# Main_3.net
KiCad netlist of a schematic drawn in Altium Designer
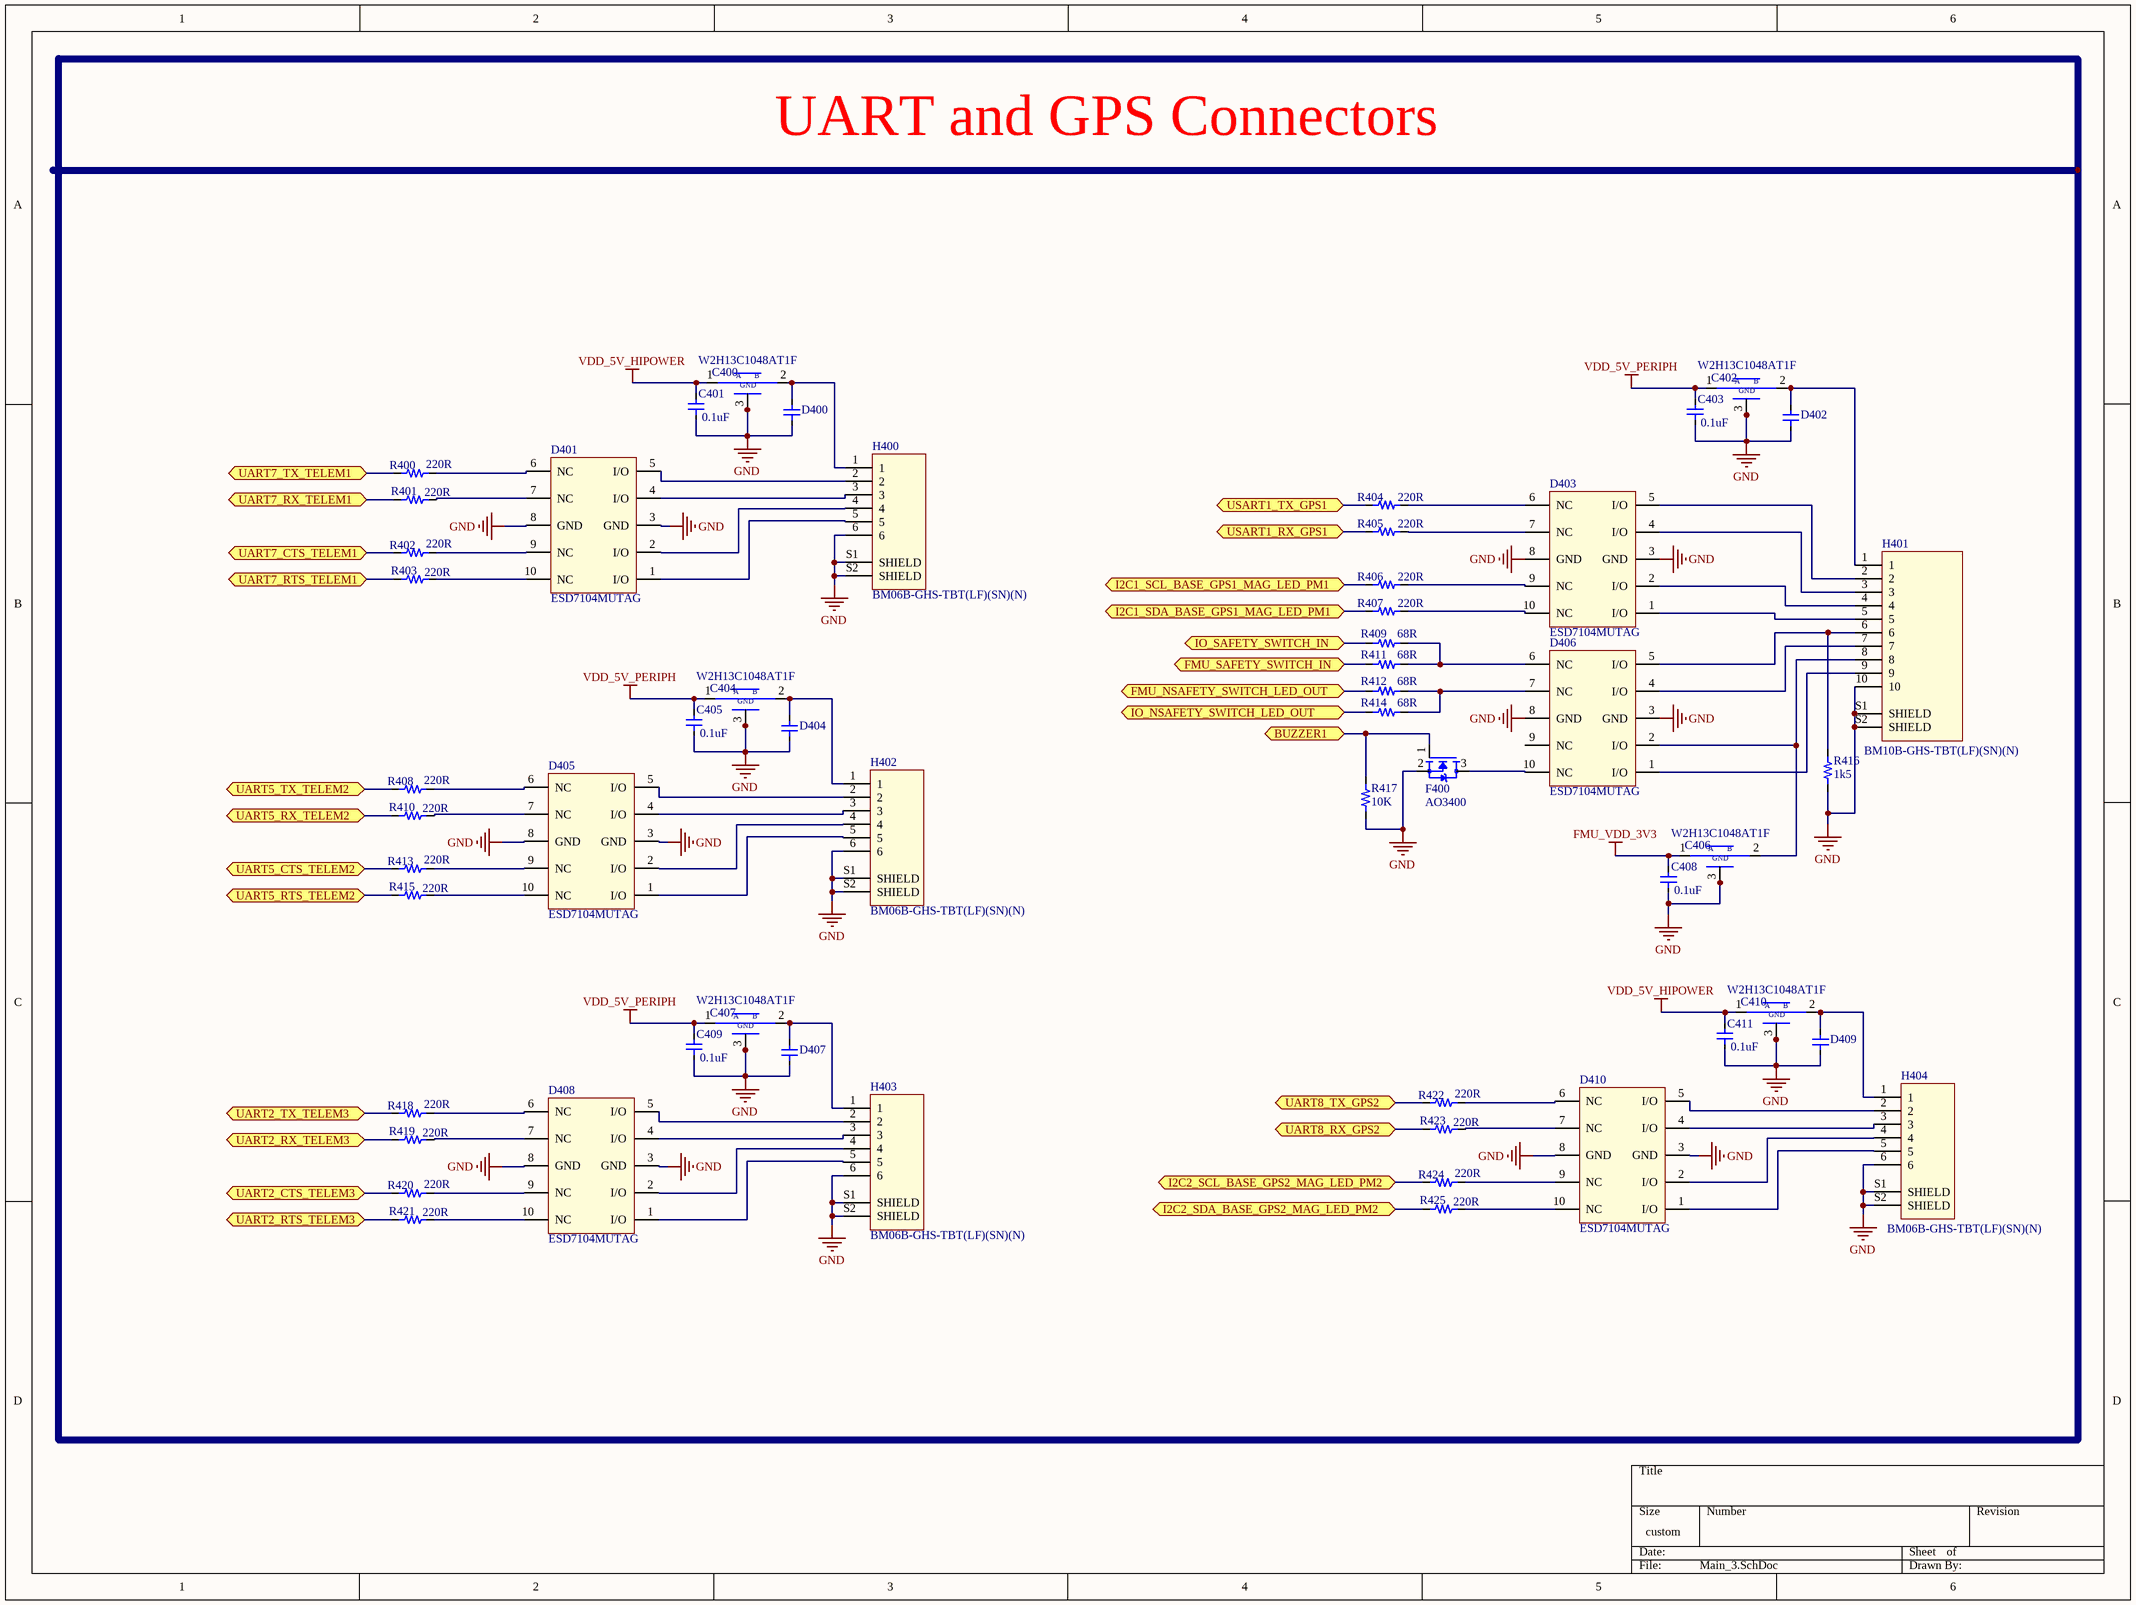
[diagram p0: Main_3.SchDoc]

(export (version "E")
  (design (tool "Eeschema 10.0.6"))
  (components
    (comp (ref "C400")
      (value "W2H13C1048AT1F")
      (footprint "W2H13C1048AT1F")
      (description "Feed Through Capacitors 25V 0.1uF X7R")
      (libsource (lib "UAV_mainboard") (part "W2H13C1048AT1F"))
    )
    (comp (ref "C401")
      (value "0.1uF")
      (footprint "C0603")
      (description "CAP CER 0.1UF 25V X7R 0603")
      (libsource (lib "UAV_mainboard") (part "CC0603KRX7R8BB104"))
    )
    (comp (ref "C402")
      (value "W2H13C1048AT1F")
      (footprint "W2H13C1048AT1F")
      (description "Feed Through Capacitors 25V 0.1uF X7R")
      (libsource (lib "UAV_mainboard") (part "W2H13C1048AT1F"))
    )
    (comp (ref "C403")
      (value "0.1uF")
      (footprint "C0603")
      (description "CAP CER 0.1UF 25V X7R 0603")
      (libsource (lib "UAV_mainboard") (part "CC0603KRX7R8BB104"))
    )
    (comp (ref "C404")
      (value "W2H13C1048AT1F")
      (footprint "W2H13C1048AT1F")
      (description "Feed Through Capacitors 25V 0.1uF X7R")
      (libsource (lib "UAV_mainboard") (part "W2H13C1048AT1F"))
    )
    (comp (ref "C405")
      (value "0.1uF")
      (footprint "C0603")
      (description "CAP CER 0.1UF 25V X7R 0603")
      (libsource (lib "UAV_mainboard") (part "CC0603KRX7R8BB104"))
    )
    (comp (ref "C406")
      (value "W2H13C1048AT1F")
      (footprint "W2H13C1048AT1F")
      (description "Feed Through Capacitors 25V 0.1uF X7R")
      (libsource (lib "UAV_mainboard") (part "W2H13C1048AT1F"))
    )
    (comp (ref "C407")
      (value "W2H13C1048AT1F")
      (footprint "W2H13C1048AT1F")
      (description "Feed Through Capacitors 25V 0.1uF X7R")
      (libsource (lib "UAV_mainboard") (part "W2H13C1048AT1F"))
    )
    (comp (ref "C408")
      (value "0.1uF")
      (footprint "C0603")
      (description "CAP CER 0.1UF 25V X7R 0603")
      (libsource (lib "UAV_mainboard") (part "CC0603KRX7R8BB104"))
    )
    (comp (ref "C409")
      (value "0.1uF")
      (footprint "C0603")
      (description "CAP CER 0.1UF 25V X7R 0603")
      (libsource (lib "UAV_mainboard") (part "CC0603KRX7R8BB104"))
    )
    (comp (ref "C410")
      (value "W2H13C1048AT1F")
      (footprint "W2H13C1048AT1F")
      (description "Feed Through Capacitors 25V 0.1uF X7R")
      (libsource (lib "UAV_mainboard") (part "W2H13C1048AT1F"))
    )
    (comp (ref "C411")
      (value "0.1uF")
      (footprint "C0603")
      (description "CAP CER 0.1UF 25V X7R 0603")
      (libsource (lib "UAV_mainboard") (part "CC0603KRX7R8BB104"))
    )
    (comp (ref "D400")
      (value "PESD0402-140")
      (footprint "PESD0402-140")
      (description "40V Clamp - Ipp Tvs Diode Surface Mount 0402")
      (libsource (lib "UAV_mainboard") (part "PESD0402-140"))
    )
    (comp (ref "D401")
      (value "ESD7104MUTAG")
      (footprint "UDFN10 2.5x1, 0.5P")
      (description "TVS DIODE 5VWM 10VC 10UDFN")
      (libsource (lib "UAV_mainboard") (part "ESD7104MUTAG"))
    )
    (comp (ref "D402")
      (value "PESD0402-140")
      (footprint "PESD0402-140")
      (description "40V Clamp - Ipp Tvs Diode Surface Mount 0402")
      (libsource (lib "UAV_mainboard") (part "PESD0402-140"))
    )
    (comp (ref "D403")
      (value "ESD7104MUTAG")
      (footprint "UDFN10 2.5x1, 0.5P")
      (description "TVS DIODE 5VWM 10VC 10UDFN")
      (libsource (lib "UAV_mainboard") (part "ESD7104MUTAG"))
    )
    (comp (ref "D404")
      (value "PESD0402-140")
      (footprint "PESD0402-140")
      (description "40V Clamp - Ipp Tvs Diode Surface Mount 0402")
      (libsource (lib "UAV_mainboard") (part "PESD0402-140"))
    )
    (comp (ref "D405")
      (value "ESD7104MUTAG")
      (footprint "UDFN10 2.5x1, 0.5P")
      (description "TVS DIODE 5VWM 10VC 10UDFN")
      (libsource (lib "UAV_mainboard") (part "ESD7104MUTAG"))
    )
    (comp (ref "D406")
      (value "ESD7104MUTAG")
      (footprint "UDFN10 2.5x1, 0.5P")
      (description "TVS DIODE 5VWM 10VC 10UDFN")
      (libsource (lib "UAV_mainboard") (part "ESD7104MUTAG"))
    )
    (comp (ref "D407")
      (value "PESD0402-140")
      (footprint "PESD0402-140")
      (description "40V Clamp - Ipp Tvs Diode Surface Mount 0402")
      (libsource (lib "UAV_mainboard") (part "PESD0402-140"))
    )
    (comp (ref "D408")
      (value "ESD7104MUTAG")
      (footprint "UDFN10 2.5x1, 0.5P")
      (description "TVS DIODE 5VWM 10VC 10UDFN")
      (libsource (lib "UAV_mainboard") (part "ESD7104MUTAG"))
    )
    (comp (ref "D409")
      (value "PESD0402-140")
      (footprint "PESD0402-140")
      (description "40V Clamp - Ipp Tvs Diode Surface Mount 0402")
      (libsource (lib "UAV_mainboard") (part "PESD0402-140"))
    )
    (comp (ref "D410")
      (value "ESD7104MUTAG")
      (footprint "UDFN10 2.5x1, 0.5P")
      (description "TVS DIODE 5VWM 10VC 10UDFN")
      (libsource (lib "UAV_mainboard") (part "ESD7104MUTAG"))
    )
    (comp (ref "F400")
      (value "AO3400")
      (footprint "SOT-23")
      (description "N-Channel 30 V 5.8A (Ta) 1.5W (Ta) Surface Mount SOT-23")
      (libsource (lib "UAV_mainboard") (part "AO3400"))
    )
    (comp (ref "H400")
      (value "BM06B-GHS-TBT(LF)(SN)(N)")
      (footprint "BM06B-GHS-TBT(LF)(SN)(N)")
      (description "Connector Header Surface Mount 6 position 0.049\" (1.25mm)")
      (libsource (lib "UAV_mainboard") (part "BM06B-GHS-TBT(LF)(SN)(N)"))
    )
    (comp (ref "H401")
      (value "BM10B-GHS-TBT(LF)(SN)(N)")
      (footprint "BM10B-GHS-TBT(LF)(SN)(N)")
      (description "Connector Header Surface Mount 10 position 0.049\" (1.25mm)")
      (libsource (lib "UAV_mainboard") (part "BM10B-GHS-TBT(LF)(SN)(N)"))
    )
    (comp (ref "H402")
      (value "BM06B-GHS-TBT(LF)(SN)(N)")
      (footprint "BM06B-GHS-TBT(LF)(SN)(N)")
      (description "Connector Header Surface Mount 6 position 0.049\" (1.25mm)")
      (libsource (lib "UAV_mainboard") (part "BM06B-GHS-TBT(LF)(SN)(N)"))
    )
    (comp (ref "H403")
      (value "BM06B-GHS-TBT(LF)(SN)(N)")
      (footprint "BM06B-GHS-TBT(LF)(SN)(N)")
      (description "Connector Header Surface Mount 6 position 0.049\" (1.25mm)")
      (libsource (lib "UAV_mainboard") (part "BM06B-GHS-TBT(LF)(SN)(N)"))
    )
    (comp (ref "H404")
      (value "BM06B-GHS-TBT(LF)(SN)(N)")
      (footprint "BM06B-GHS-TBT(LF)(SN)(N)")
      (description "Connector Header Surface Mount 6 position 0.049\" (1.25mm)")
      (libsource (lib "UAV_mainboard") (part "BM06B-GHS-TBT(LF)(SN)(N)"))
    )
    (comp (ref "R400")
      (value "220R")
      (footprint "R0402")
      (description "RES 220 OHM 1% 1/16W 0402")
      (libsource (lib "UAV_mainboard") (part "RC0402FR-07220RL"))
    )
    (comp (ref "R401")
      (value "220R")
      (footprint "R0402")
      (description "RES 220 OHM 1% 1/16W 0402")
      (libsource (lib "UAV_mainboard") (part "RC0402FR-07220RL"))
    )
    (comp (ref "R402")
      (value "220R")
      (footprint "R0402")
      (description "RES 220 OHM 1% 1/16W 0402")
      (libsource (lib "UAV_mainboard") (part "RC0402FR-07220RL"))
    )
    (comp (ref "R403")
      (value "220R")
      (footprint "R0402")
      (description "RES 220 OHM 1% 1/16W 0402")
      (libsource (lib "UAV_mainboard") (part "RC0402FR-07220RL"))
    )
    (comp (ref "R404")
      (value "220R")
      (footprint "R0402")
      (description "RES 220 OHM 1% 1/16W 0402")
      (libsource (lib "UAV_mainboard") (part "RC0402FR-07220RL"))
    )
    (comp (ref "R405")
      (value "220R")
      (footprint "R0402")
      (description "RES 220 OHM 1% 1/16W 0402")
      (libsource (lib "UAV_mainboard") (part "RC0402FR-07220RL"))
    )
    (comp (ref "R406")
      (value "220R")
      (footprint "R0402")
      (description "RES 220 OHM 1% 1/16W 0402")
      (libsource (lib "UAV_mainboard") (part "RC0402FR-07220RL"))
    )
    (comp (ref "R407")
      (value "220R")
      (footprint "R0402")
      (description "RES 220 OHM 1% 1/16W 0402")
      (libsource (lib "UAV_mainboard") (part "RC0402FR-07220RL"))
    )
    (comp (ref "R408")
      (value "220R")
      (footprint "R0402")
      (description "RES 220 OHM 1% 1/16W 0402")
      (libsource (lib "UAV_mainboard") (part "RC0402FR-07220RL"))
    )
    (comp (ref "R409")
      (value "68R")
      (footprint "R0402")
      (description "68 Ohms ±1% 0.063W, 1/16W Chip Resistor 0402 (1005 Metric) Moisture Resistant Thick Film")
      (libsource (lib "UAV_mainboard") (part "RC0402FR-0768RL"))
    )
    (comp (ref "R410")
      (value "220R")
      (footprint "R0402")
      (description "RES 220 OHM 1% 1/16W 0402")
      (libsource (lib "UAV_mainboard") (part "RC0402FR-07220RL"))
    )
    (comp (ref "R411")
      (value "68R")
      (footprint "R0402")
      (description "68 Ohms ±1% 0.063W, 1/16W Chip Resistor 0402 (1005 Metric) Moisture Resistant Thick Film")
      (libsource (lib "UAV_mainboard") (part "RC0402FR-0768RL"))
    )
    (comp (ref "R412")
      (value "68R")
      (footprint "R0402")
      (description "68 Ohms ±1% 0.063W, 1/16W Chip Resistor 0402 (1005 Metric) Moisture Resistant Thick Film")
      (libsource (lib "UAV_mainboard") (part "RC0402FR-0768RL"))
    )
    (comp (ref "R413")
      (value "220R")
      (footprint "R0402")
      (description "RES 220 OHM 1% 1/16W 0402")
      (libsource (lib "UAV_mainboard") (part "RC0402FR-07220RL"))
    )
    (comp (ref "R414")
      (value "68R")
      (footprint "R0402")
      (description "68 Ohms ±1% 0.063W, 1/16W Chip Resistor 0402 (1005 Metric) Moisture Resistant Thick Film")
      (libsource (lib "UAV_mainboard") (part "RC0402FR-0768RL"))
    )
    (comp (ref "R415")
      (value "220R")
      (footprint "R0402")
      (description "RES 220 OHM 1% 1/16W 0402")
      (libsource (lib "UAV_mainboard") (part "RC0402FR-07220RL"))
    )
    (comp (ref "R416")
      (value "1k5")
      (footprint "R0402")
      (description "1.5 kOhms ±1% 0.063W, 1/16W Chip Resistor 0402 (1005 Metric) Thick Film")
      (libsource (lib "UAV_mainboard") (part "RC0402FR-131K5L"))
    )
    (comp (ref "R417")
      (value "10K")
      (footprint "R0402")
      (description "RES SMD 10K OHM 1% 1/16W 0402")
      (libsource (lib "UAV_mainboard") (part "RC1005F103CS"))
    )
    (comp (ref "R418")
      (value "220R")
      (footprint "R0402")
      (description "RES 220 OHM 1% 1/16W 0402")
      (libsource (lib "UAV_mainboard") (part "RC0402FR-07220RL"))
    )
    (comp (ref "R419")
      (value "220R")
      (footprint "R0402")
      (description "RES 220 OHM 1% 1/16W 0402")
      (libsource (lib "UAV_mainboard") (part "RC0402FR-07220RL"))
    )
    (comp (ref "R420")
      (value "220R")
      (footprint "R0402")
      (description "RES 220 OHM 1% 1/16W 0402")
      (libsource (lib "UAV_mainboard") (part "RC0402FR-07220RL"))
    )
    (comp (ref "R421")
      (value "220R")
      (footprint "R0402")
      (description "RES 220 OHM 1% 1/16W 0402")
      (libsource (lib "UAV_mainboard") (part "RC0402FR-07220RL"))
    )
    (comp (ref "R422")
      (value "220R")
      (footprint "R0402")
      (description "RES 220 OHM 1% 1/16W 0402")
      (libsource (lib "UAV_mainboard") (part "RC0402FR-07220RL"))
    )
    (comp (ref "R423")
      (value "220R")
      (footprint "R0402")
      (description "RES 220 OHM 1% 1/16W 0402")
      (libsource (lib "UAV_mainboard") (part "RC0402FR-07220RL"))
    )
    (comp (ref "R424")
      (value "220R")
      (footprint "R0402")
      (description "RES 220 OHM 1% 1/16W 0402")
      (libsource (lib "UAV_mainboard") (part "RC0402FR-07220RL"))
    )
    (comp (ref "R425")
      (value "220R")
      (footprint "R0402")
      (description "RES 220 OHM 1% 1/16W 0402")
      (libsource (lib "UAV_mainboard") (part "RC0402FR-07220RL"))
    )
  )
  (nets
    (net (code "1") (name "/BUZZER1") (class "Default")
      (node (ref "F400") (pin "1") (pinfunction "G_1") (pintype "passive"))
      (node (ref "R417") (pin "2") (pinfunction "2_2") (pintype "passive"))
    )
    (net (code "2") (name "/FMU_NSAFETY_SWITCH_LED_OUT") (class "Default")
      (node (ref "R412") (pin "1") (pinfunction "1_1") (pintype "passive"))
    )
    (net (code "3") (name "/FMU_SAFETY_SWITCH_IN") (class "Default")
      (node (ref "R411") (pin "1") (pinfunction "1_1") (pintype "passive"))
    )
    (net (code "4") (name "/I2C1_SCL_BASE_GPS1_MAG_LED_PM1") (class "Default")
      (node (ref "R406") (pin "1") (pinfunction "1_1") (pintype "passive"))
    )
    (net (code "5") (name "/I2C1_SDA_BASE_GPS1_MAG_LED_PM1") (class "Default")
      (node (ref "R407") (pin "1") (pinfunction "1_1") (pintype "passive"))
    )
    (net (code "6") (name "/I2C2_SCL_BASE_GPS2_MAG_LED_PM2") (class "Default")
      (node (ref "R424") (pin "1") (pinfunction "1_1") (pintype "passive"))
    )
    (net (code "7") (name "/I2C2_SDA_BASE_GPS2_MAG_LED_PM2") (class "Default")
      (node (ref "R425") (pin "1") (pinfunction "1_1") (pintype "passive"))
    )
    (net (code "8") (name "/IO_NSAFETY_SWITCH_LED_OUT") (class "Default")
      (node (ref "R414") (pin "1") (pinfunction "1_1") (pintype "passive"))
    )
    (net (code "9") (name "/IO_SAFETY_SWITCH_IN") (class "Default")
      (node (ref "R409") (pin "1") (pinfunction "1_1") (pintype "passive"))
    )
    (net (code "10") (name "/UART2_CTS_TELEM3") (class "Default")
      (node (ref "R420") (pin "1") (pinfunction "1_1") (pintype "passive"))
    )
    (net (code "11") (name "/UART2_RTS_TELEM3") (class "Default")
      (node (ref "R421") (pin "1") (pinfunction "1_1") (pintype "passive"))
    )
    (net (code "12") (name "/UART2_RX_TELEM3") (class "Default")
      (node (ref "R419") (pin "1") (pinfunction "1_1") (pintype "passive"))
    )
    (net (code "13") (name "/UART2_TX_TELEM3") (class "Default")
      (node (ref "R418") (pin "1") (pinfunction "1_1") (pintype "passive"))
    )
    (net (code "14") (name "/UART5_CTS_TELEM2") (class "Default")
      (node (ref "R413") (pin "1") (pinfunction "1_1") (pintype "passive"))
    )
    (net (code "15") (name "/UART5_RTS_TELEM2") (class "Default")
      (node (ref "R415") (pin "1") (pinfunction "1_1") (pintype "passive"))
    )
    (net (code "16") (name "/UART5_RX_TELEM2") (class "Default")
      (node (ref "R410") (pin "1") (pinfunction "1_1") (pintype "passive"))
    )
    (net (code "17") (name "/UART5_TX_TELEM2") (class "Default")
      (node (ref "R408") (pin "1") (pinfunction "1_1") (pintype "passive"))
    )
    (net (code "18") (name "/UART7_CTS_TELEM1") (class "Default")
      (node (ref "R402") (pin "1") (pinfunction "1_1") (pintype "passive"))
    )
    (net (code "19") (name "/UART7_RTS_TELEM1") (class "Default")
      (node (ref "R403") (pin "1") (pinfunction "1_1") (pintype "passive"))
    )
    (net (code "20") (name "/UART7_RX_TELEM1") (class "Default")
      (node (ref "R401") (pin "1") (pinfunction "1_1") (pintype "passive"))
    )
    (net (code "21") (name "/UART7_TX_TELEM1") (class "Default")
      (node (ref "R400") (pin "1") (pinfunction "1_1") (pintype "passive"))
    )
    (net (code "22") (name "/UART8_RX_GPS2") (class "Default")
      (node (ref "R423") (pin "1") (pinfunction "1_1") (pintype "passive"))
    )
    (net (code "23") (name "/UART8_TX_GPS2") (class "Default")
      (node (ref "R422") (pin "1") (pinfunction "1_1") (pintype "passive"))
    )
    (net (code "24") (name "/USART1_RX_GPS1") (class "Default")
      (node (ref "R405") (pin "1") (pinfunction "1_1") (pintype "passive"))
    )
    (net (code "25") (name "/USART1_TX_GPS1") (class "Default")
      (node (ref "R404") (pin "1") (pinfunction "1_1") (pintype "passive"))
    )
    (net (code "26") (name "FMU_VDD_3V3") (class "Default")
      (node (ref "C406") (pin "1") (pintype "passive"))
      (node (ref "C408") (pin "2") (pinfunction "2_2") (pintype "passive"))
    )
    (net (code "27") (name "GND") (class "Default")
      (node (ref "C400") (pin "3") (pintype "passive"))
      (node (ref "C400") (pin "4") (pinfunction "4_4") (pintype "passive"))
      (node (ref "C401") (pin "1") (pinfunction "1_1") (pintype "passive"))
      (node (ref "C402") (pin "3") (pintype "passive"))
      (node (ref "C402") (pin "4") (pinfunction "4_4") (pintype "passive"))
      (node (ref "C403") (pin "1") (pinfunction "1_1") (pintype "passive"))
      (node (ref "C404") (pin "3") (pintype "passive"))
      (node (ref "C404") (pin "4") (pinfunction "4_4") (pintype "passive"))
      (node (ref "C405") (pin "1") (pinfunction "1_1") (pintype "passive"))
      (node (ref "C406") (pin "3") (pintype "passive"))
      (node (ref "C406") (pin "4") (pinfunction "4_4") (pintype "passive"))
      (node (ref "C407") (pin "3") (pintype "passive"))
      (node (ref "C407") (pin "4") (pinfunction "4_4") (pintype "passive"))
      (node (ref "C408") (pin "1") (pinfunction "1_1") (pintype "passive"))
      (node (ref "C409") (pin "1") (pinfunction "1_1") (pintype "passive"))
      (node (ref "C410") (pin "3") (pintype "passive"))
      (node (ref "C410") (pin "4") (pinfunction "4_4") (pintype "passive"))
      (node (ref "C411") (pin "1") (pinfunction "1_1") (pintype "passive"))
      (node (ref "D400") (pin "1") (pinfunction "1_1") (pintype "passive"))
      (node (ref "D401") (pin "3") (pinfunction "GND_3") (pintype "passive"))
      (node (ref "D401") (pin "8") (pinfunction "GND_8") (pintype "passive"))
      (node (ref "D402") (pin "1") (pinfunction "1_1") (pintype "passive"))
      (node (ref "D403") (pin "3") (pinfunction "GND_3") (pintype "passive"))
      (node (ref "D403") (pin "8") (pinfunction "GND_8") (pintype "passive"))
      (node (ref "D404") (pin "1") (pinfunction "1_1") (pintype "passive"))
      (node (ref "D405") (pin "3") (pinfunction "GND_3") (pintype "passive"))
      (node (ref "D405") (pin "8") (pinfunction "GND_8") (pintype "passive"))
      (node (ref "D406") (pin "3") (pinfunction "GND_3") (pintype "passive"))
      (node (ref "D406") (pin "8") (pinfunction "GND_8") (pintype "passive"))
      (node (ref "D407") (pin "1") (pinfunction "1_1") (pintype "passive"))
      (node (ref "D408") (pin "3") (pinfunction "GND_3") (pintype "passive"))
      (node (ref "D408") (pin "8") (pinfunction "GND_8") (pintype "passive"))
      (node (ref "D409") (pin "1") (pinfunction "1_1") (pintype "passive"))
      (node (ref "D410") (pin "3") (pinfunction "GND_3") (pintype "passive"))
      (node (ref "D410") (pin "8") (pinfunction "GND_8") (pintype "passive"))
      (node (ref "F400") (pin "2") (pinfunction "S_2") (pintype "passive"))
      (node (ref "H400") (pin "6") (pinfunction "6_6") (pintype "passive"))
      (node (ref "H400") (pin "S1") (pinfunction "SHIELD_S1") (pintype "passive"))
      (node (ref "H400") (pin "S2") (pinfunction "SHIELD_S2") (pintype "passive"))
      (node (ref "H401") (pin "10") (pinfunction "10_10") (pintype "passive"))
      (node (ref "H401") (pin "S1") (pinfunction "SHIELD_S1") (pintype "passive"))
      (node (ref "H401") (pin "S2") (pinfunction "SHIELD_S2") (pintype "passive"))
      (node (ref "H402") (pin "6") (pinfunction "6_6") (pintype "passive"))
      (node (ref "H402") (pin "S1") (pinfunction "SHIELD_S1") (pintype "passive"))
      (node (ref "H402") (pin "S2") (pinfunction "SHIELD_S2") (pintype "passive"))
      (node (ref "H403") (pin "6") (pinfunction "6_6") (pintype "passive"))
      (node (ref "H403") (pin "S1") (pinfunction "SHIELD_S1") (pintype "passive"))
      (node (ref "H403") (pin "S2") (pinfunction "SHIELD_S2") (pintype "passive"))
      (node (ref "H404") (pin "6") (pinfunction "6_6") (pintype "passive"))
      (node (ref "H404") (pin "S1") (pinfunction "SHIELD_S1") (pintype "passive"))
      (node (ref "H404") (pin "S2") (pinfunction "SHIELD_S2") (pintype "passive"))
      (node (ref "R416") (pin "1") (pinfunction "1_1") (pintype "passive"))
      (node (ref "R417") (pin "1") (pinfunction "1_1") (pintype "passive"))
    )
    (net (code "28") (name "Net-(C400-Pad2)") (class "Default")
      (node (ref "C400") (pin "2") (pintype "passive"))
      (node (ref "D400") (pin "2") (pinfunction "2_2") (pintype "passive"))
      (node (ref "H400") (pin "1") (pinfunction "1_1") (pintype "passive"))
    )
    (net (code "29") (name "Net-(C402-Pad2)") (class "Default")
      (node (ref "C402") (pin "2") (pintype "passive"))
      (node (ref "D402") (pin "2") (pinfunction "2_2") (pintype "passive"))
      (node (ref "H401") (pin "1") (pinfunction "1_1") (pintype "passive"))
    )
    (net (code "30") (name "Net-(C404-Pad2)") (class "Default")
      (node (ref "C404") (pin "2") (pintype "passive"))
      (node (ref "D404") (pin "2") (pinfunction "2_2") (pintype "passive"))
      (node (ref "H402") (pin "1") (pinfunction "1_1") (pintype "passive"))
    )
    (net (code "31") (name "Net-(C406-Pad2)") (class "Default")
      (node (ref "C406") (pin "2") (pintype "passive"))
      (node (ref "D406") (pin "2") (pinfunction "I/O_2") (pintype "passive"))
      (node (ref "H401") (pin "8") (pinfunction "8_8") (pintype "passive"))
    )
    (net (code "32") (name "Net-(C407-Pad2)") (class "Default")
      (node (ref "C407") (pin "2") (pintype "passive"))
      (node (ref "D407") (pin "2") (pinfunction "2_2") (pintype "passive"))
      (node (ref "H403") (pin "1") (pinfunction "1_1") (pintype "passive"))
    )
    (net (code "33") (name "Net-(C410-Pad2)") (class "Default")
      (node (ref "C410") (pin "2") (pintype "passive"))
      (node (ref "D409") (pin "2") (pinfunction "2_2") (pintype "passive"))
      (node (ref "H404") (pin "1") (pinfunction "1_1") (pintype "passive"))
    )
    (net (code "34") (name "Net-(D401-I{slash}O-Pad1)") (class "Default")
      (node (ref "D401") (pin "1") (pinfunction "I/O_1") (pintype "passive"))
      (node (ref "H400") (pin "5") (pinfunction "5_5") (pintype "passive"))
    )
    (net (code "35") (name "Net-(D401-I{slash}O-Pad2)") (class "Default")
      (node (ref "D401") (pin "2") (pinfunction "I/O_2") (pintype "passive"))
      (node (ref "H400") (pin "4") (pinfunction "4_4") (pintype "passive"))
    )
    (net (code "36") (name "Net-(D401-I{slash}O-Pad4)") (class "Default")
      (node (ref "D401") (pin "4") (pinfunction "I/O_4") (pintype "passive"))
      (node (ref "H400") (pin "3") (pinfunction "3_3") (pintype "passive"))
    )
    (net (code "37") (name "Net-(D401-I{slash}O-Pad5)") (class "Default")
      (node (ref "D401") (pin "5") (pinfunction "I/O_5") (pintype "passive"))
      (node (ref "H400") (pin "2") (pinfunction "2_2") (pintype "passive"))
    )
    (net (code "38") (name "Net-(D401-NC-Pad6)") (class "Default")
      (node (ref "D401") (pin "6") (pinfunction "NC_6") (pintype "passive"))
      (node (ref "R400") (pin "2") (pinfunction "2_2") (pintype "passive"))
    )
    (net (code "39") (name "Net-(D401-NC-Pad7)") (class "Default")
      (node (ref "D401") (pin "7") (pinfunction "NC_7") (pintype "passive"))
      (node (ref "R401") (pin "2") (pinfunction "2_2") (pintype "passive"))
    )
    (net (code "40") (name "Net-(D401-NC-Pad9)") (class "Default")
      (node (ref "D401") (pin "9") (pinfunction "NC_9") (pintype "passive"))
      (node (ref "R402") (pin "2") (pinfunction "2_2") (pintype "passive"))
    )
    (net (code "41") (name "Net-(D401-NC-Pad10)") (class "Default")
      (node (ref "D401") (pin "10") (pinfunction "NC_10") (pintype "passive"))
      (node (ref "R403") (pin "2") (pinfunction "2_2") (pintype "passive"))
    )
    (net (code "42") (name "Net-(D403-I{slash}O-Pad1)") (class "Default")
      (node (ref "D403") (pin "1") (pinfunction "I/O_1") (pintype "passive"))
      (node (ref "H401") (pin "5") (pinfunction "5_5") (pintype "passive"))
    )
    (net (code "43") (name "Net-(D403-I{slash}O-Pad2)") (class "Default")
      (node (ref "D403") (pin "2") (pinfunction "I/O_2") (pintype "passive"))
      (node (ref "H401") (pin "4") (pinfunction "4_4") (pintype "passive"))
    )
    (net (code "44") (name "Net-(D403-I{slash}O-Pad4)") (class "Default")
      (node (ref "D403") (pin "4") (pinfunction "I/O_4") (pintype "passive"))
      (node (ref "H401") (pin "3") (pinfunction "3_3") (pintype "passive"))
    )
    (net (code "45") (name "Net-(D403-I{slash}O-Pad5)") (class "Default")
      (node (ref "D403") (pin "5") (pinfunction "I/O_5") (pintype "passive"))
      (node (ref "H401") (pin "2") (pinfunction "2_2") (pintype "passive"))
    )
    (net (code "46") (name "Net-(D403-NC-Pad6)") (class "Default")
      (node (ref "D403") (pin "6") (pinfunction "NC_6") (pintype "passive"))
      (node (ref "R404") (pin "2") (pinfunction "2_2") (pintype "passive"))
    )
    (net (code "47") (name "Net-(D403-NC-Pad7)") (class "Default")
      (node (ref "D403") (pin "7") (pinfunction "NC_7") (pintype "passive"))
      (node (ref "R405") (pin "2") (pinfunction "2_2") (pintype "passive"))
    )
    (net (code "48") (name "Net-(D403-NC-Pad9)") (class "Default")
      (node (ref "D403") (pin "9") (pinfunction "NC_9") (pintype "passive"))
      (node (ref "R406") (pin "2") (pinfunction "2_2") (pintype "passive"))
    )
    (net (code "49") (name "Net-(D403-NC-Pad10)") (class "Default")
      (node (ref "D403") (pin "10") (pinfunction "NC_10") (pintype "passive"))
      (node (ref "R407") (pin "2") (pinfunction "2_2") (pintype "passive"))
    )
    (net (code "50") (name "Net-(D405-I{slash}O-Pad1)") (class "Default")
      (node (ref "D405") (pin "1") (pinfunction "I/O_1") (pintype "passive"))
      (node (ref "H402") (pin "5") (pinfunction "5_5") (pintype "passive"))
    )
    (net (code "51") (name "Net-(D405-I{slash}O-Pad2)") (class "Default")
      (node (ref "D405") (pin "2") (pinfunction "I/O_2") (pintype "passive"))
      (node (ref "H402") (pin "4") (pinfunction "4_4") (pintype "passive"))
    )
    (net (code "52") (name "Net-(D405-I{slash}O-Pad4)") (class "Default")
      (node (ref "D405") (pin "4") (pinfunction "I/O_4") (pintype "passive"))
      (node (ref "H402") (pin "3") (pinfunction "3_3") (pintype "passive"))
    )
    (net (code "53") (name "Net-(D405-I{slash}O-Pad5)") (class "Default")
      (node (ref "D405") (pin "5") (pinfunction "I/O_5") (pintype "passive"))
      (node (ref "H402") (pin "2") (pinfunction "2_2") (pintype "passive"))
    )
    (net (code "54") (name "Net-(D405-NC-Pad6)") (class "Default")
      (node (ref "D405") (pin "6") (pinfunction "NC_6") (pintype "passive"))
      (node (ref "R408") (pin "2") (pinfunction "2_2") (pintype "passive"))
    )
    (net (code "55") (name "Net-(D405-NC-Pad7)") (class "Default")
      (node (ref "D405") (pin "7") (pinfunction "NC_7") (pintype "passive"))
      (node (ref "R410") (pin "2") (pinfunction "2_2") (pintype "passive"))
    )
    (net (code "56") (name "Net-(D405-NC-Pad9)") (class "Default")
      (node (ref "D405") (pin "9") (pinfunction "NC_9") (pintype "passive"))
      (node (ref "R413") (pin "2") (pinfunction "2_2") (pintype "passive"))
    )
    (net (code "57") (name "Net-(D405-NC-Pad10)") (class "Default")
      (node (ref "D405") (pin "10") (pinfunction "NC_10") (pintype "passive"))
      (node (ref "R415") (pin "2") (pinfunction "2_2") (pintype "passive"))
    )
    (net (code "58") (name "Net-(D406-I{slash}O-Pad1)") (class "Default")
      (node (ref "D406") (pin "1") (pinfunction "I/O_1") (pintype "passive"))
      (node (ref "H401") (pin "9") (pinfunction "9_9") (pintype "passive"))
    )
    (net (code "59") (name "Net-(D406-I{slash}O-Pad4)") (class "Default")
      (node (ref "D406") (pin "4") (pinfunction "I/O_4") (pintype "passive"))
      (node (ref "H401") (pin "7") (pinfunction "7_7") (pintype "passive"))
    )
    (net (code "60") (name "Net-(D406-I{slash}O-Pad5)") (class "Default")
      (node (ref "D406") (pin "5") (pinfunction "I/O_5") (pintype "passive"))
      (node (ref "H401") (pin "6") (pinfunction "6_6") (pintype "passive"))
      (node (ref "R416") (pin "2") (pinfunction "2_2") (pintype "passive"))
    )
    (net (code "61") (name "Net-(D406-NC-Pad6)") (class "Default")
      (node (ref "D406") (pin "6") (pinfunction "NC_6") (pintype "passive"))
      (node (ref "R409") (pin "2") (pinfunction "2_2") (pintype "passive"))
      (node (ref "R411") (pin "2") (pinfunction "2_2") (pintype "passive"))
    )
    (net (code "62") (name "Net-(D406-NC-Pad7)") (class "Default")
      (node (ref "D406") (pin "7") (pinfunction "NC_7") (pintype "passive"))
      (node (ref "R412") (pin "2") (pinfunction "2_2") (pintype "passive"))
      (node (ref "R414") (pin "2") (pinfunction "2_2") (pintype "passive"))
    )
    (net (code "63") (name "Net-(D408-I{slash}O-Pad1)") (class "Default")
      (node (ref "D408") (pin "1") (pinfunction "I/O_1") (pintype "passive"))
      (node (ref "H403") (pin "5") (pinfunction "5_5") (pintype "passive"))
    )
    (net (code "64") (name "Net-(D408-I{slash}O-Pad2)") (class "Default")
      (node (ref "D408") (pin "2") (pinfunction "I/O_2") (pintype "passive"))
      (node (ref "H403") (pin "4") (pinfunction "4_4") (pintype "passive"))
    )
    (net (code "65") (name "Net-(D408-I{slash}O-Pad4)") (class "Default")
      (node (ref "D408") (pin "4") (pinfunction "I/O_4") (pintype "passive"))
      (node (ref "H403") (pin "3") (pinfunction "3_3") (pintype "passive"))
    )
    (net (code "66") (name "Net-(D408-I{slash}O-Pad5)") (class "Default")
      (node (ref "D408") (pin "5") (pinfunction "I/O_5") (pintype "passive"))
      (node (ref "H403") (pin "2") (pinfunction "2_2") (pintype "passive"))
    )
    (net (code "67") (name "Net-(D408-NC-Pad6)") (class "Default")
      (node (ref "D408") (pin "6") (pinfunction "NC_6") (pintype "passive"))
      (node (ref "R418") (pin "2") (pinfunction "2_2") (pintype "passive"))
    )
    (net (code "68") (name "Net-(D408-NC-Pad7)") (class "Default")
      (node (ref "D408") (pin "7") (pinfunction "NC_7") (pintype "passive"))
      (node (ref "R419") (pin "2") (pinfunction "2_2") (pintype "passive"))
    )
    (net (code "69") (name "Net-(D408-NC-Pad9)") (class "Default")
      (node (ref "D408") (pin "9") (pinfunction "NC_9") (pintype "passive"))
      (node (ref "R420") (pin "2") (pinfunction "2_2") (pintype "passive"))
    )
    (net (code "70") (name "Net-(D408-NC-Pad10)") (class "Default")
      (node (ref "D408") (pin "10") (pinfunction "NC_10") (pintype "passive"))
      (node (ref "R421") (pin "2") (pinfunction "2_2") (pintype "passive"))
    )
    (net (code "71") (name "Net-(D410-I{slash}O-Pad1)") (class "Default")
      (node (ref "D410") (pin "1") (pinfunction "I/O_1") (pintype "passive"))
      (node (ref "H404") (pin "5") (pinfunction "5_5") (pintype "passive"))
    )
    (net (code "72") (name "Net-(D410-I{slash}O-Pad2)") (class "Default")
      (node (ref "D410") (pin "2") (pinfunction "I/O_2") (pintype "passive"))
      (node (ref "H404") (pin "4") (pinfunction "4_4") (pintype "passive"))
    )
    (net (code "73") (name "Net-(D410-I{slash}O-Pad4)") (class "Default")
      (node (ref "D410") (pin "4") (pinfunction "I/O_4") (pintype "passive"))
      (node (ref "H404") (pin "3") (pinfunction "3_3") (pintype "passive"))
    )
    (net (code "74") (name "Net-(D410-I{slash}O-Pad5)") (class "Default")
      (node (ref "D410") (pin "5") (pinfunction "I/O_5") (pintype "passive"))
      (node (ref "H404") (pin "2") (pinfunction "2_2") (pintype "passive"))
    )
    (net (code "75") (name "Net-(D410-NC-Pad6)") (class "Default")
      (node (ref "D410") (pin "6") (pinfunction "NC_6") (pintype "passive"))
      (node (ref "R422") (pin "2") (pinfunction "2_2") (pintype "passive"))
    )
    (net (code "76") (name "Net-(D410-NC-Pad7)") (class "Default")
      (node (ref "D410") (pin "7") (pinfunction "NC_7") (pintype "passive"))
      (node (ref "R423") (pin "2") (pinfunction "2_2") (pintype "passive"))
    )
    (net (code "77") (name "Net-(D410-NC-Pad9)") (class "Default")
      (node (ref "D410") (pin "9") (pinfunction "NC_9") (pintype "passive"))
      (node (ref "R424") (pin "2") (pinfunction "2_2") (pintype "passive"))
    )
    (net (code "78") (name "Net-(D410-NC-Pad10)") (class "Default")
      (node (ref "D410") (pin "10") (pinfunction "NC_10") (pintype "passive"))
      (node (ref "R425") (pin "2") (pinfunction "2_2") (pintype "passive"))
    )
    (net (code "79") (name "Net-(F400-D)") (class "Default")
      (node (ref "D406") (pin "10") (pinfunction "NC_10") (pintype "passive"))
      (node (ref "F400") (pin "3") (pinfunction "D_3") (pintype "passive"))
    )
    (net (code "80") (name "VDD_5V_HIPOWER") (class "Default")
      (node (ref "C400") (pin "1") (pintype "passive"))
      (node (ref "C401") (pin "2") (pinfunction "2_2") (pintype "passive"))
      (node (ref "C410") (pin "1") (pintype "passive"))
      (node (ref "C411") (pin "2") (pinfunction "2_2") (pintype "passive"))
    )
    (net (code "81") (name "VDD_5V_PERIPH") (class "Default")
      (node (ref "C402") (pin "1") (pintype "passive"))
      (node (ref "C403") (pin "2") (pinfunction "2_2") (pintype "passive"))
      (node (ref "C404") (pin "1") (pintype "passive"))
      (node (ref "C405") (pin "2") (pinfunction "2_2") (pintype "passive"))
      (node (ref "C407") (pin "1") (pintype "passive"))
      (node (ref "C409") (pin "2") (pinfunction "2_2") (pintype "passive"))
    )
    (net (code "82") (name "unconnected-(D406-NC-Pad9)") (class "Default")
      (node (ref "D406") (pin "9") (pinfunction "NC_9") (pintype "passive"))
    )
  )
)
